# sew_pads.net
KiCad netlist of a schematic drawn in EAGLE
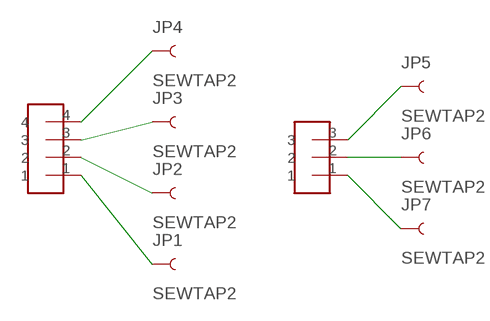
[diagram p0: schematic, sheet 1]

(export (version "E")
  (design (tool "Eeschema 10.0.6"))
  (components
    (comp (ref "JP1")
      (value "SEWTAP2")
      (footprint "eagle-import:PETAL-LONG-2")
      (libsource (lib "eagle-import") (part "SEWTAP2"))
    )
    (comp (ref "JP2")
      (value "SEWTAP2")
      (footprint "eagle-import:PETAL-LONG-2")
      (libsource (lib "eagle-import") (part "SEWTAP2"))
    )
    (comp (ref "JP3")
      (value "SEWTAP2")
      (footprint "eagle-import:PETAL-LONG-2")
      (libsource (lib "eagle-import") (part "SEWTAP2"))
    )
    (comp (ref "JP4")
      (value "SEWTAP2")
      (footprint "eagle-import:PETAL-LONG-2")
      (libsource (lib "eagle-import") (part "SEWTAP2"))
    )
    (comp (ref "JP5")
      (value "SEWTAP2")
      (footprint "eagle-import:PETAL-LONG-2")
      (libsource (lib "eagle-import") (part "SEWTAP2"))
    )
    (comp (ref "JP6")
      (value "SEWTAP2")
      (footprint "eagle-import:PETAL-LONG-2")
      (libsource (lib "eagle-import") (part "SEWTAP2"))
    )
    (comp (ref "JP7")
      (value "SEWTAP2")
      (footprint "eagle-import:PETAL-LONG-2")
      (libsource (lib "eagle-import") (part "SEWTAP2"))
    )
    (comp (ref "U$1")
      (value "HEADER-3")
      (footprint "eagle-import:HEADER-3")
      (libsource (lib "eagle-import") (part "HEADER-3"))
    )
    (comp (ref "U$2")
      (value "HEADER-4")
      (footprint "eagle-import:HEADER-4")
      (libsource (lib "eagle-import") (part "HEADER-4"))
    )
  )
  (nets
    (net (code "1") (name "Net-(JP1-Pad1)") (class "Default")
      (node (ref "JP1") (pin "1") (pinfunction "1_1") (pintype "bidirectional"))
      (node (ref "U$2") (pin "1") (pinfunction "1_1") (pintype "bidirectional"))
    )
    (net (code "2") (name "Net-(JP2-Pad1)") (class "Default")
      (node (ref "JP2") (pin "1") (pinfunction "1_1") (pintype "bidirectional"))
      (node (ref "U$2") (pin "2") (pinfunction "2_2") (pintype "bidirectional"))
    )
    (net (code "3") (name "Net-(JP3-Pad1)") (class "Default")
      (node (ref "JP3") (pin "1") (pinfunction "1_1") (pintype "bidirectional"))
      (node (ref "U$2") (pin "3") (pinfunction "3_3") (pintype "bidirectional"))
    )
    (net (code "4") (name "Net-(JP4-Pad1)") (class "Default")
      (node (ref "JP4") (pin "1") (pinfunction "1_1") (pintype "bidirectional"))
      (node (ref "U$2") (pin "4") (pinfunction "4_4") (pintype "bidirectional"))
    )
    (net (code "5") (name "Net-(JP5-Pad1)") (class "Default")
      (node (ref "JP5") (pin "1") (pinfunction "1_1") (pintype "bidirectional"))
      (node (ref "U$1") (pin "3") (pinfunction "3_3") (pintype "bidirectional"))
    )
    (net (code "6") (name "Net-(JP6-Pad1)") (class "Default")
      (node (ref "JP6") (pin "1") (pinfunction "1_1") (pintype "bidirectional"))
      (node (ref "U$1") (pin "2") (pinfunction "2_2") (pintype "bidirectional"))
    )
    (net (code "7") (name "Net-(JP7-Pad1)") (class "Default")
      (node (ref "JP7") (pin "1") (pinfunction "1_1") (pintype "bidirectional"))
      (node (ref "U$1") (pin "1") (pinfunction "1_1") (pintype "bidirectional"))
    )
  )
)
